# Status_Board_0_4.net
KiCad netlist of a schematic drawn in EAGLE
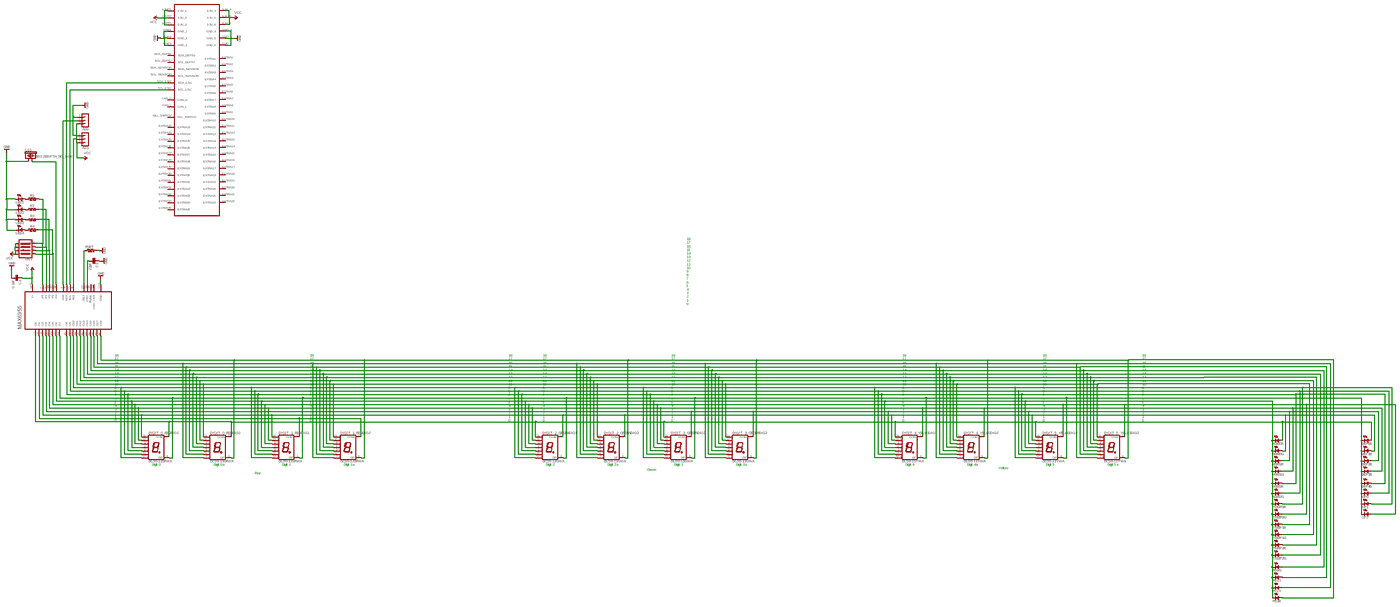
[diagram p0: schematic, sheet 1, overview]
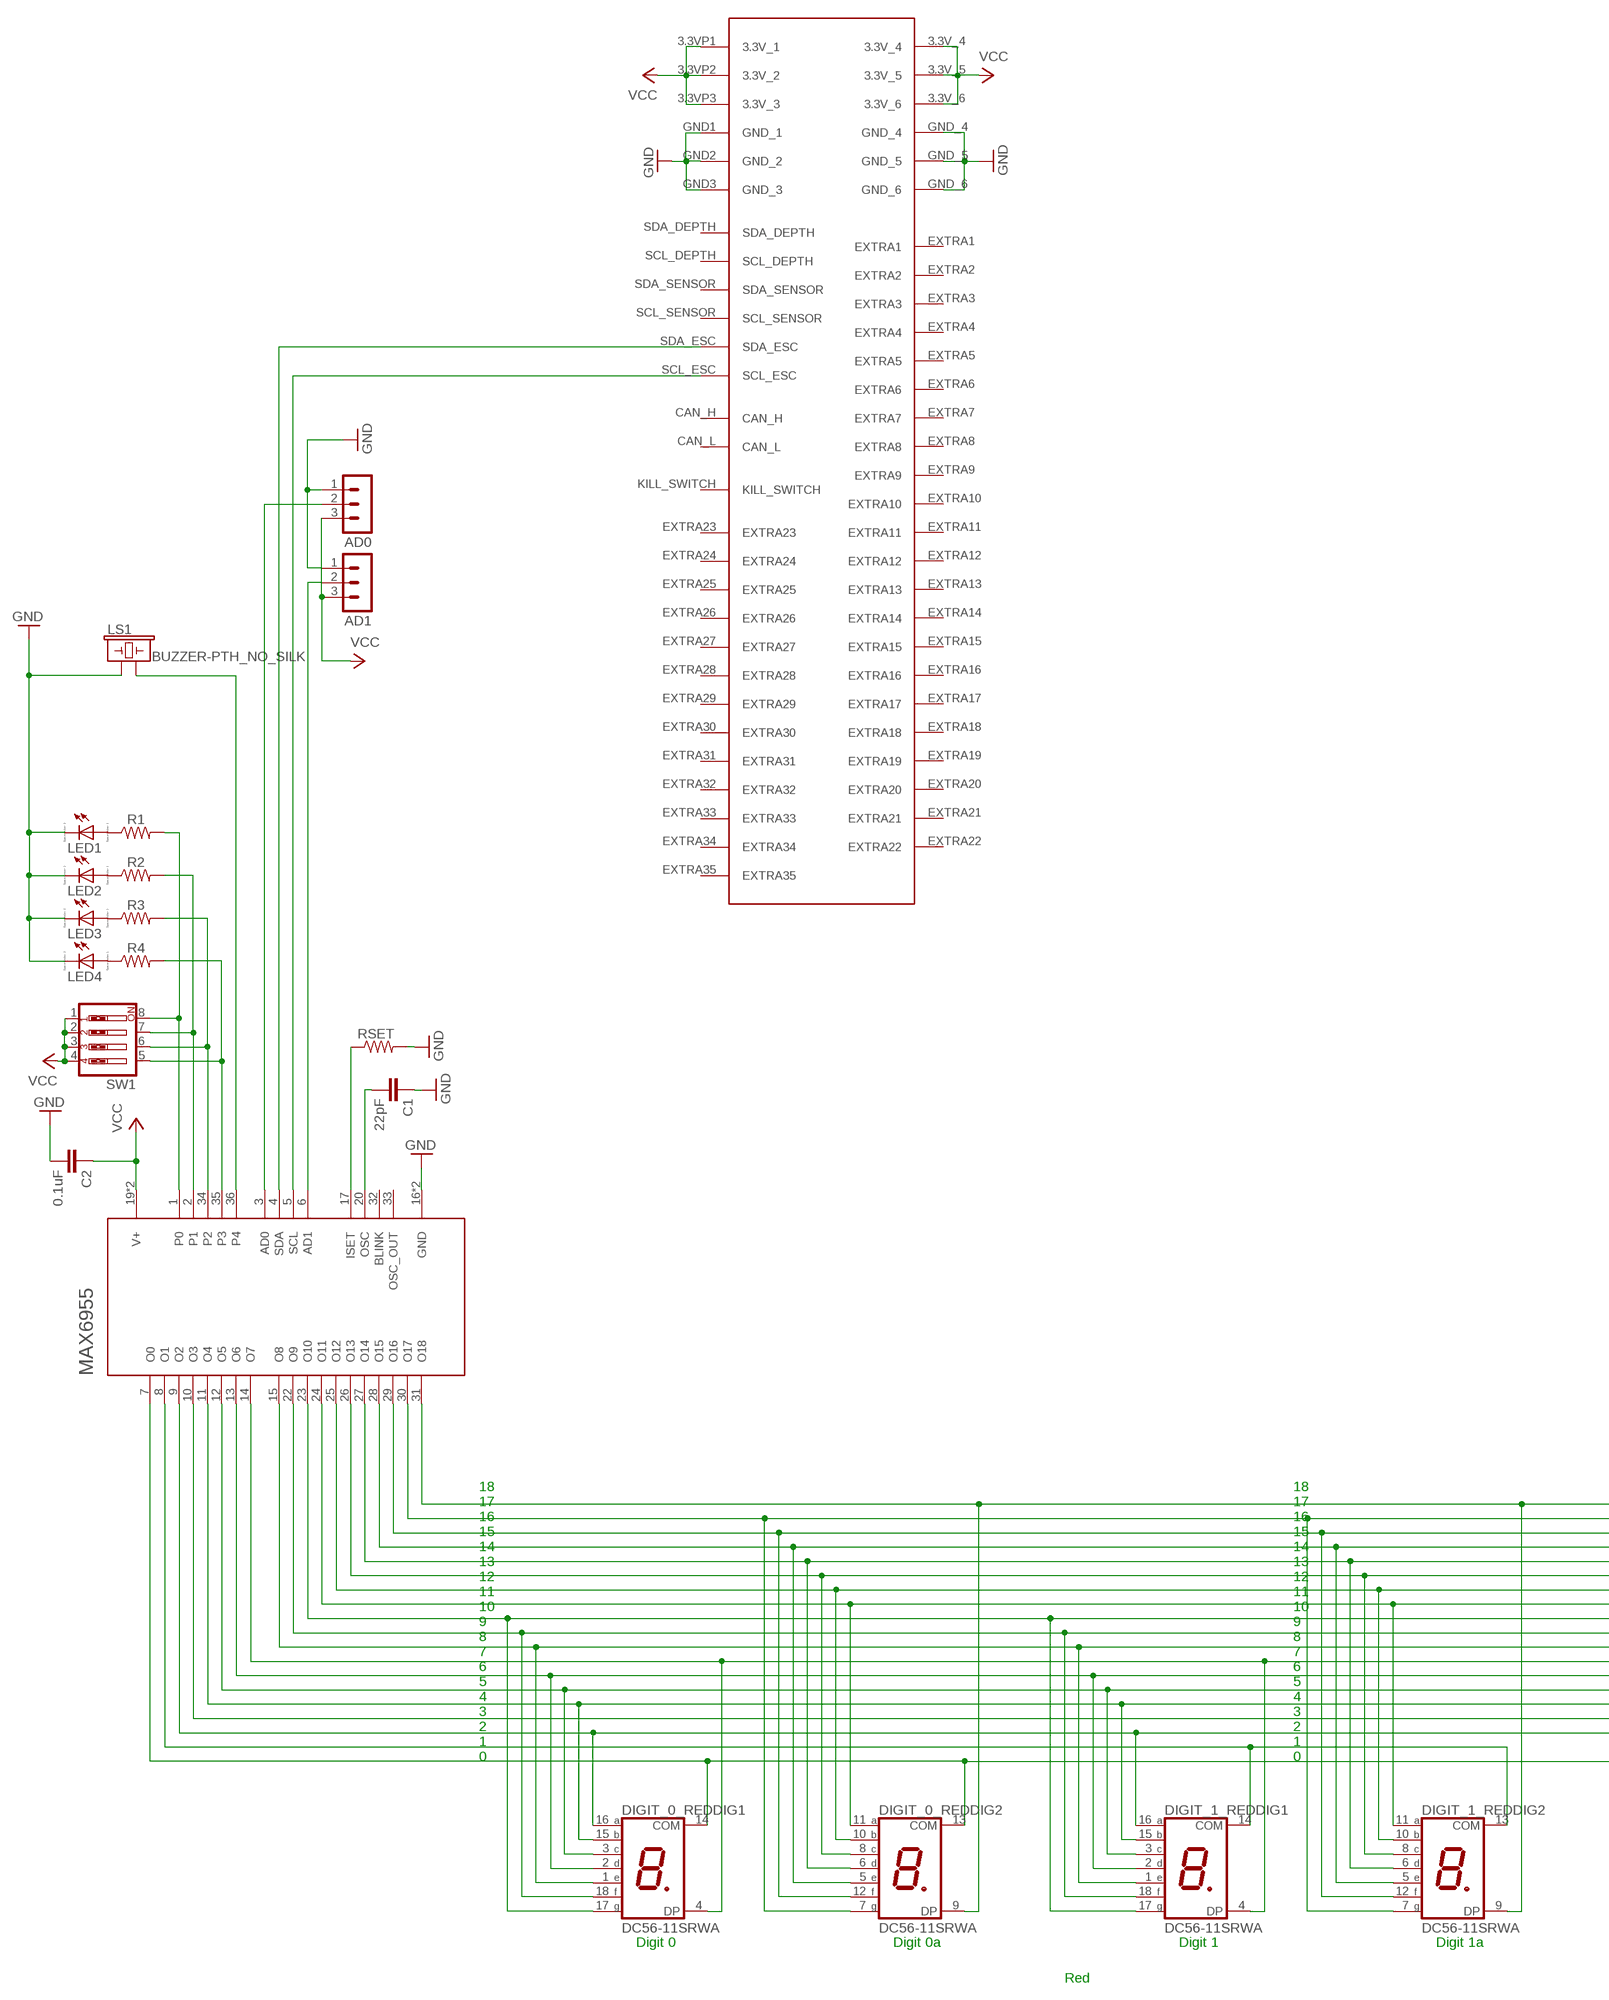
[diagram p1: schematic, sheet 1, part 1 of 4]
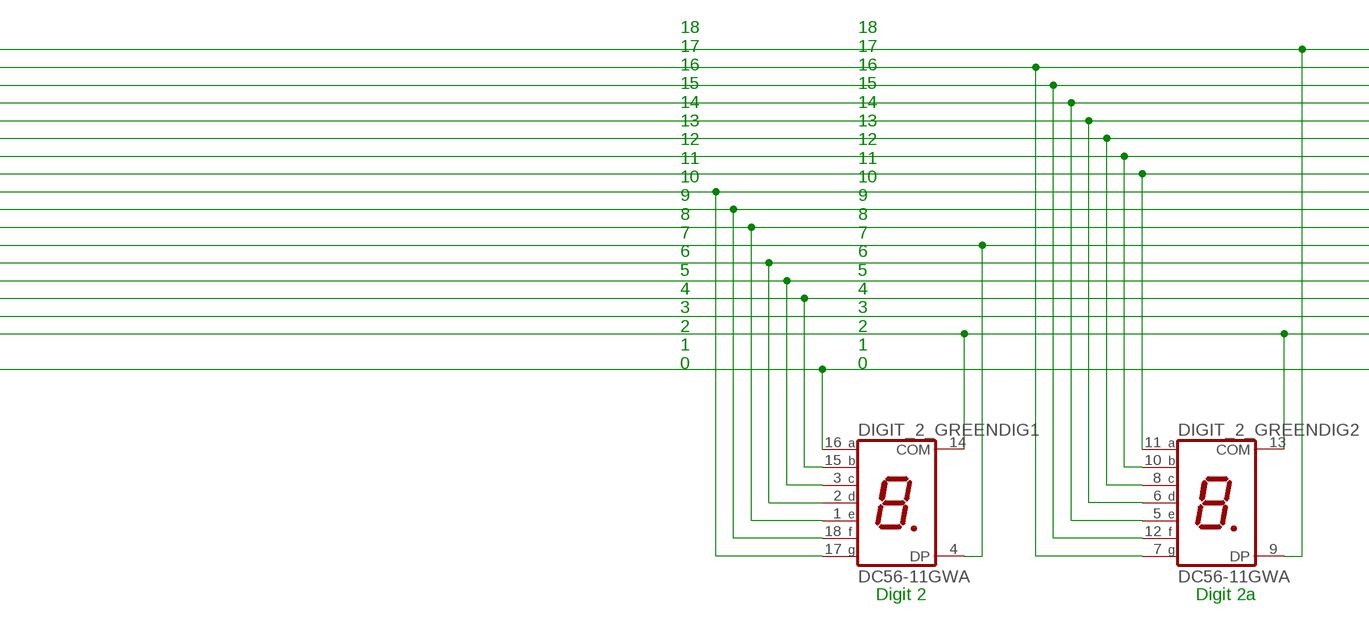
[diagram p2: schematic, sheet 1, part 2 of 4]
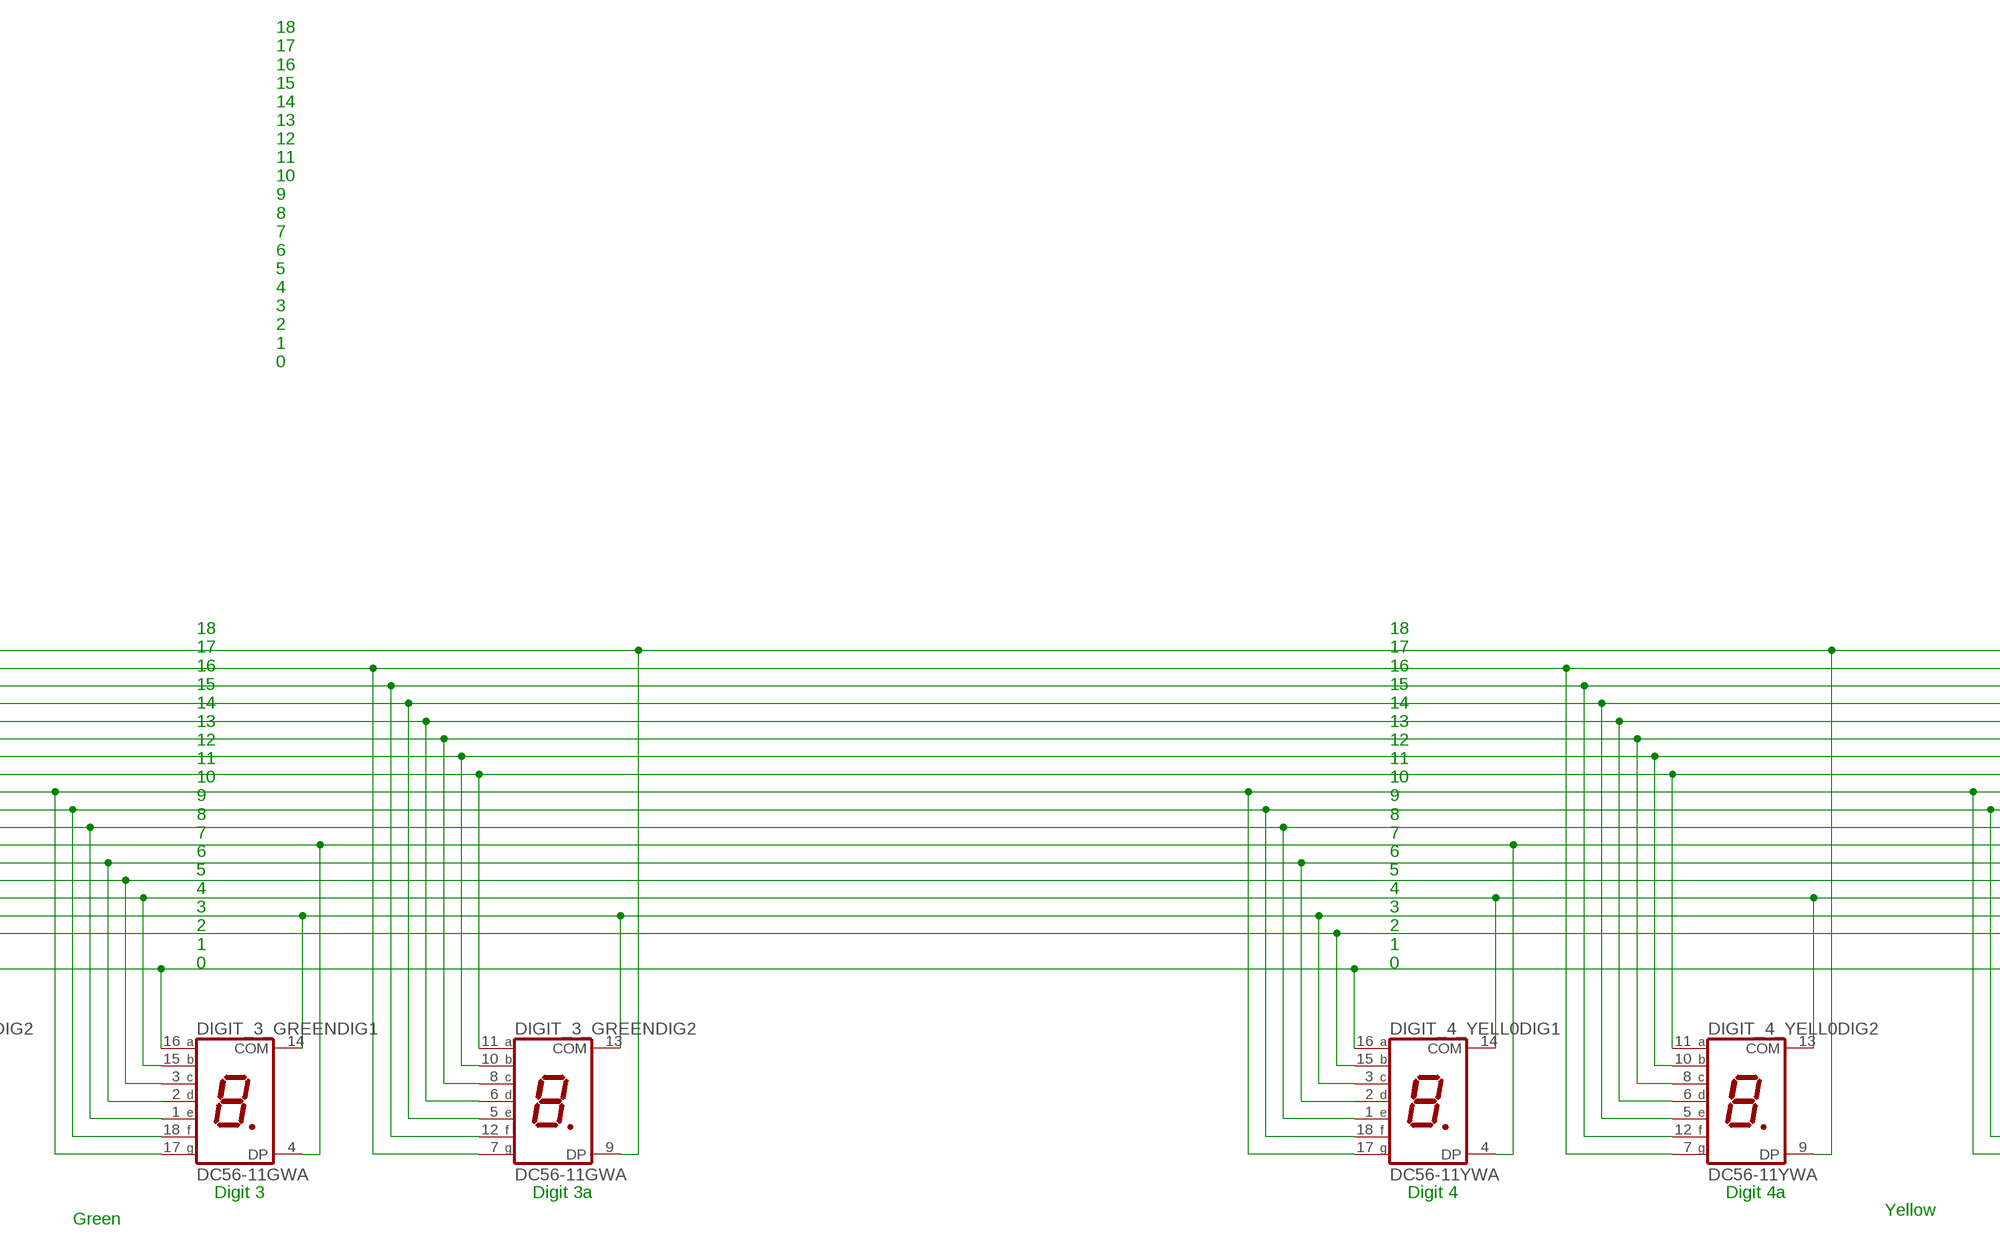
[diagram p3: schematic, sheet 1, part 3 of 4]
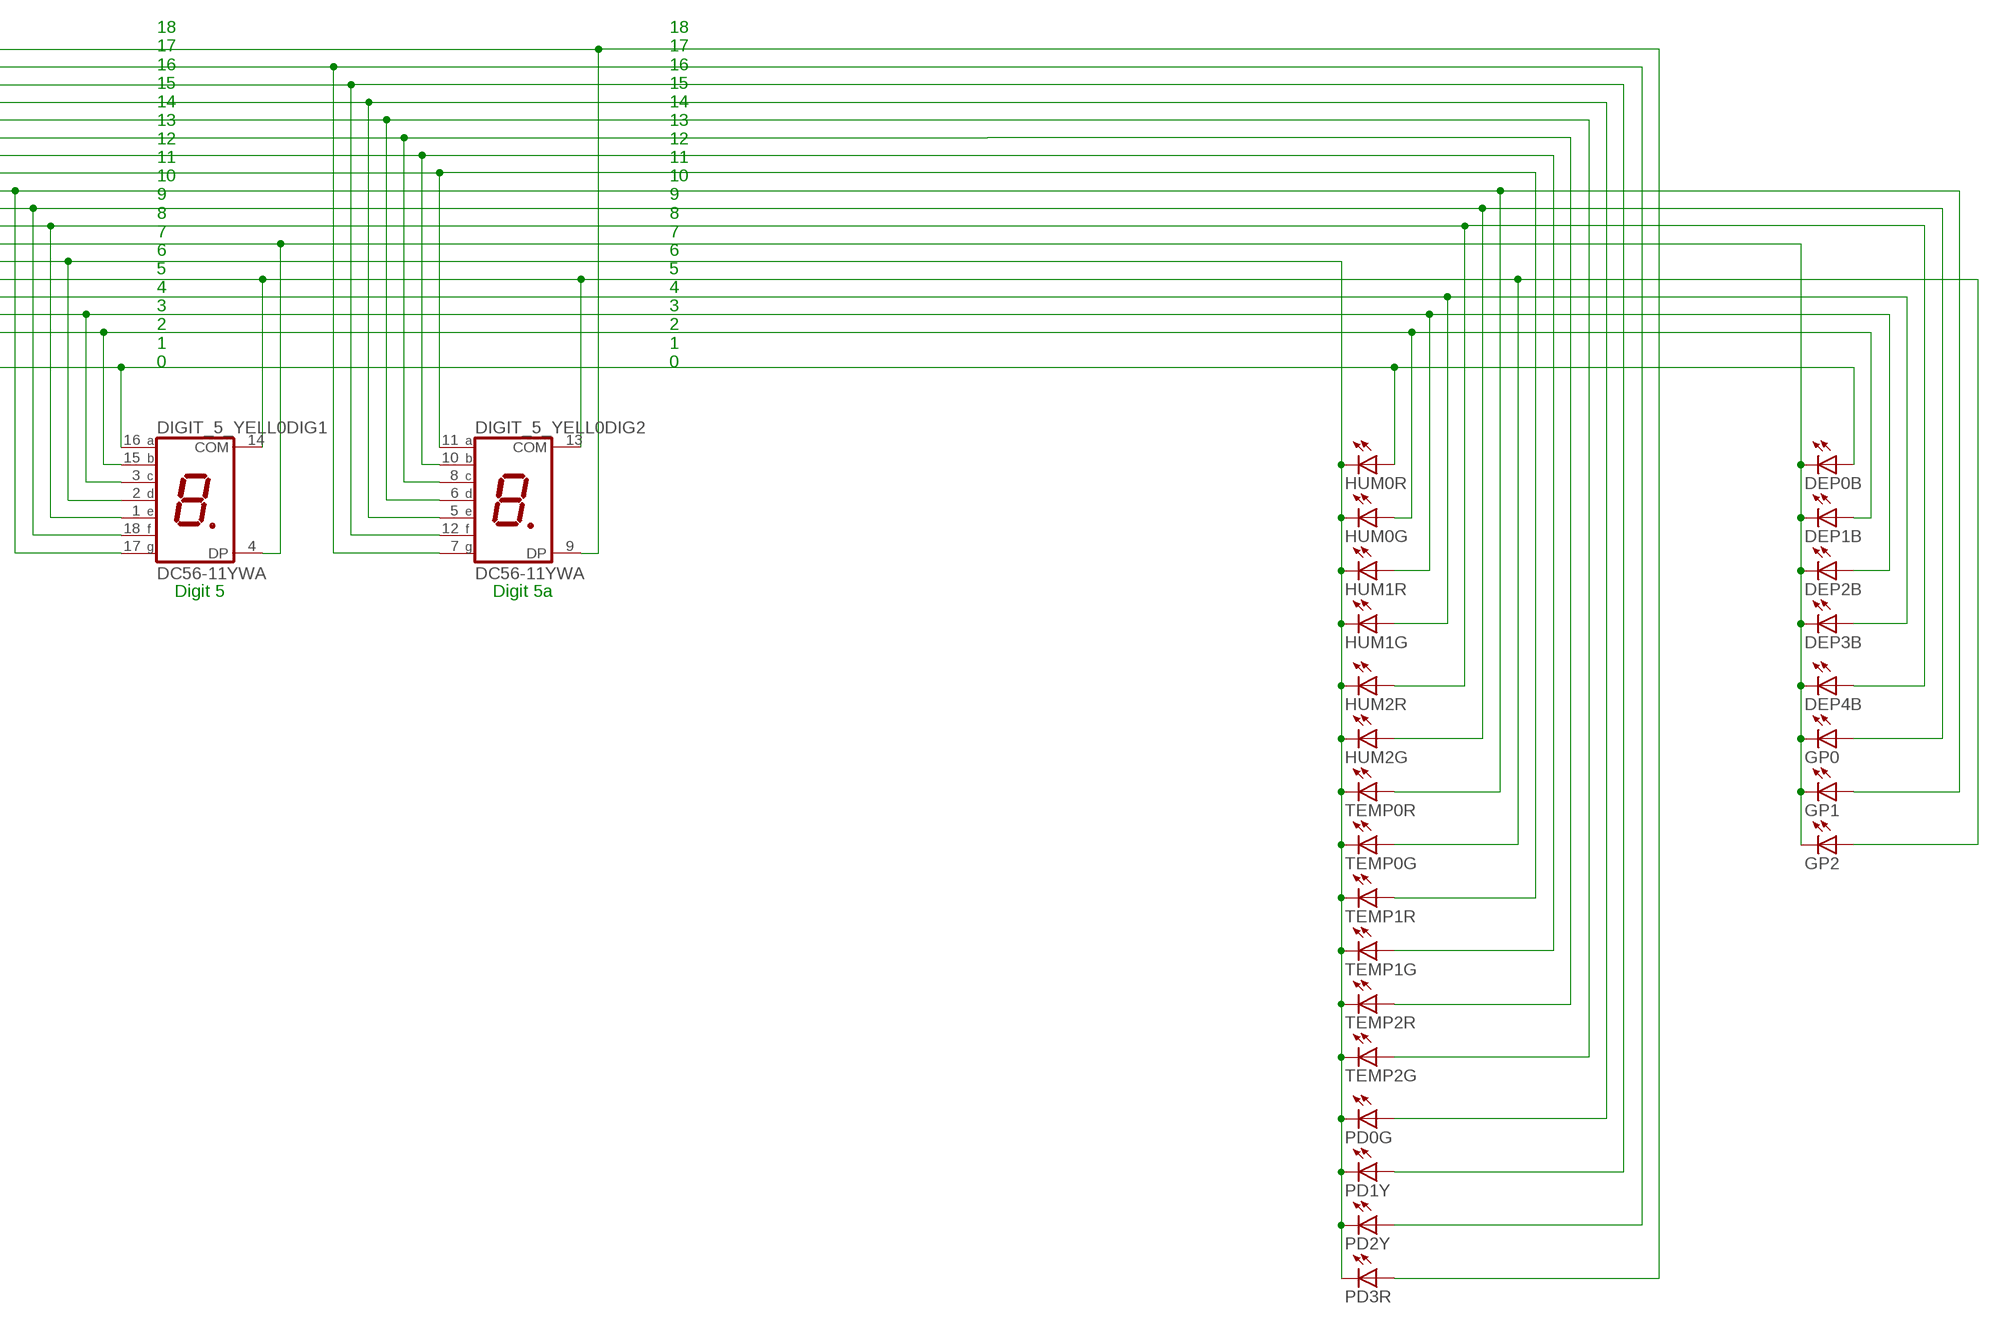
[diagram p4: schematic, sheet 1, part 4 of 4]

(export (version "E")
  (design (tool "Eeschema 10.0.6"))
  (components
    (comp (ref "AD0")
      (value "MA03-1")
      (footprint "eagle-import:MA03-1")
      (libsource (lib "eagle-import") (part "MA03-1"))
    )
    (comp (ref "AD1")
      (value "MA03-1")
      (footprint "eagle-import:MA03-1")
      (libsource (lib "eagle-import") (part "MA03-1"))
    )
    (comp (ref "C1")
      (value "22pF")
      (footprint "eagle-import:CAP-PTH-2.54")
      (libsource (lib "eagle-import") (part "22PF-PTH-2.54MM-200V-5%"))
    )
    (comp (ref "C2")
      (value "0.1uF")
      (footprint "eagle-import:CAP-PTH-SMALL-KIT")
      (libsource (lib "eagle-import") (part "0.1UF-KIT-EZ-50V-20%"))
    )
    (comp (ref "DEP0B")
      (value "LED3MM")
      (footprint "eagle-import:LED3MM")
      (libsource (lib "eagle-import") (part "LED3MM"))
    )
    (comp (ref "DEP1B")
      (value "LED3MM")
      (footprint "eagle-import:LED3MM")
      (libsource (lib "eagle-import") (part "LED3MM"))
    )
    (comp (ref "DEP2B")
      (value "LED3MM")
      (footprint "eagle-import:LED3MM")
      (libsource (lib "eagle-import") (part "LED3MM"))
    )
    (comp (ref "DEP3B")
      (value "LED3MM")
      (footprint "eagle-import:LED3MM")
      (libsource (lib "eagle-import") (part "LED3MM"))
    )
    (comp (ref "DEP4B")
      (value "LED3MM")
      (footprint "eagle-import:LED3MM")
      (libsource (lib "eagle-import") (part "LED3MM"))
    )
    (comp (ref "DIGIT_0_RED")
      (value "DC56-11SRWA")
      (footprint "eagle-import:DA56")
      (libsource (lib "eagle-import") (part "DC56-11SRWA"))
    )
    (comp (ref "DIGIT_1_RED")
      (value "DC56-11SRWA")
      (footprint "eagle-import:DA56")
      (libsource (lib "eagle-import") (part "DC56-11SRWA"))
    )
    (comp (ref "DIGIT_2_GREEN")
      (value "DC56-11GWA")
      (footprint "eagle-import:DA56")
      (libsource (lib "eagle-import") (part "DC56-11GWA"))
    )
    (comp (ref "DIGIT_3_GREEN")
      (value "DC56-11GWA")
      (footprint "eagle-import:DA56")
      (libsource (lib "eagle-import") (part "DC56-11GWA"))
    )
    (comp (ref "DIGIT_4_YELL0")
      (value "DC56-11YWA")
      (footprint "eagle-import:DA56")
      (libsource (lib "eagle-import") (part "DC56-11YWA"))
    )
    (comp (ref "DIGIT_5_YELL0")
      (value "DC56-11YWA")
      (footprint "eagle-import:DA56")
      (libsource (lib "eagle-import") (part "DC56-11YWA"))
    )
    (comp (ref "GP0")
      (value "LED3MM")
      (footprint "eagle-import:LED3MM")
      (libsource (lib "eagle-import") (part "LED3MM"))
    )
    (comp (ref "GP1")
      (value "LED3MM")
      (footprint "eagle-import:LED3MM")
      (libsource (lib "eagle-import") (part "LED3MM"))
    )
    (comp (ref "GP2")
      (value "LED3MM")
      (footprint "eagle-import:LED3MM")
      (libsource (lib "eagle-import") (part "LED3MM"))
    )
    (comp (ref "HUM0G")
      (value "LED3MM")
      (footprint "eagle-import:LED3MM")
      (libsource (lib "eagle-import") (part "LED3MM"))
    )
    (comp (ref "HUM0R")
      (value "LED3MM")
      (footprint "eagle-import:LED3MM")
      (libsource (lib "eagle-import") (part "LED3MM"))
    )
    (comp (ref "HUM1G")
      (value "LED3MM")
      (footprint "eagle-import:LED3MM")
      (libsource (lib "eagle-import") (part "LED3MM"))
    )
    (comp (ref "HUM1R")
      (value "LED3MM")
      (footprint "eagle-import:LED3MM")
      (libsource (lib "eagle-import") (part "LED3MM"))
    )
    (comp (ref "HUM2G")
      (value "LED3MM")
      (footprint "eagle-import:LED3MM")
      (libsource (lib "eagle-import") (part "LED3MM"))
    )
    (comp (ref "HUM2R")
      (value "LED3MM")
      (footprint "eagle-import:LED3MM")
      (libsource (lib "eagle-import") (part "LED3MM"))
    )
    (comp (ref "LED1")
      (value "LED_ESML0603")
      (footprint "eagle-import:LED_SML0603")
      (libsource (lib "eagle-import") (part "LED_ESML0603"))
    )
    (comp (ref "LED2")
      (value "LED_ESML0603")
      (footprint "eagle-import:LED_SML0603")
      (libsource (lib "eagle-import") (part "LED_ESML0603"))
    )
    (comp (ref "LED3")
      (value "LED_ESML0603")
      (footprint "eagle-import:LED_SML0603")
      (libsource (lib "eagle-import") (part "LED_ESML0603"))
    )
    (comp (ref "LED4")
      (value "LED_ESML0603")
      (footprint "eagle-import:LED_SML0603")
      (libsource (lib "eagle-import") (part "LED_ESML0603"))
    )
    (comp (ref "LS1")
      (value "BUZZER-PTH_NO_SILK")
      (footprint "eagle-import:BUZZER-12MM-NS")
      (libsource (lib "eagle-import") (part "BUZZER-PTH_NO_SILK"))
    )
    (comp (ref "MAX6955")
      (value "MAX6955")
      (footprint "eagle-import:SSOP36")
      (libsource (lib "eagle-import") (part "MAX6955"))
    )
    (comp (ref "PD0G")
      (value "LED3MM")
      (footprint "eagle-import:LED3MM")
      (libsource (lib "eagle-import") (part "LED3MM"))
    )
    (comp (ref "PD1Y")
      (value "LED3MM")
      (footprint "eagle-import:LED3MM")
      (libsource (lib "eagle-import") (part "LED3MM"))
    )
    (comp (ref "PD2Y")
      (value "LED3MM")
      (footprint "eagle-import:LED3MM")
      (libsource (lib "eagle-import") (part "LED3MM"))
    )
    (comp (ref "PD3R")
      (value "LED3MM")
      (footprint "eagle-import:LED3MM")
      (libsource (lib "eagle-import") (part "LED3MM"))
    )
    (comp (ref "R1")
      (value "68OHM-0603-1/10W-1%")
      (footprint "eagle-import:0603")
      (libsource (lib "eagle-import") (part "68OHM-0603-1/10W-1%"))
    )
    (comp (ref "R2")
      (value "68OHM-0603-1/10W-1%")
      (footprint "eagle-import:0603")
      (libsource (lib "eagle-import") (part "68OHM-0603-1/10W-1%"))
    )
    (comp (ref "R3")
      (value "68OHM-0603-1/10W-1%")
      (footprint "eagle-import:0603")
      (libsource (lib "eagle-import") (part "68OHM-0603-1/10W-1%"))
    )
    (comp (ref "R4")
      (value "68OHM-0603-1/10W-1%")
      (footprint "eagle-import:0603")
      (libsource (lib "eagle-import") (part "68OHM-0603-1/10W-1%"))
    )
    (comp (ref "RSET")
      (value "R-US_0207/12")
      (footprint "eagle-import:0207_12")
      (libsource (lib "eagle-import") (part "R-US_0207/12"))
    )
    (comp (ref "SW1")
      (value "SW_DIP-4")
      (footprint "eagle-import:EDG-04")
      (libsource (lib "eagle-import") (part "SW_DIP-4"))
    )
    (comp (ref "TEMP0G")
      (value "LED3MM")
      (footprint "eagle-import:LED3MM")
      (libsource (lib "eagle-import") (part "LED3MM"))
    )
    (comp (ref "TEMP0R")
      (value "LED3MM")
      (footprint "eagle-import:LED3MM")
      (libsource (lib "eagle-import") (part "LED3MM"))
    )
    (comp (ref "TEMP1G")
      (value "LED3MM")
      (footprint "eagle-import:LED3MM")
      (libsource (lib "eagle-import") (part "LED3MM"))
    )
    (comp (ref "TEMP1R")
      (value "LED3MM")
      (footprint "eagle-import:LED3MM")
      (libsource (lib "eagle-import") (part "LED3MM"))
    )
    (comp (ref "TEMP2G")
      (value "LED3MM")
      (footprint "eagle-import:LED3MM")
      (libsource (lib "eagle-import") (part "LED3MM"))
    )
    (comp (ref "TEMP2R")
      (value "LED3MM")
      (footprint "eagle-import:LED3MM")
      (libsource (lib "eagle-import") (part "LED3MM"))
    )
    (comp (ref "U$2")
      (value "5530843")
      (footprint "eagle-import:5530843-6-BOARDFINGERS")
      (libsource (lib "eagle-import") (part "5530843"))
    )
  )
  (nets
    (net (code "1") (name "GND") (class "Default")
      (node (ref "AD0") (pin "1") (pinfunction "1_1") (pintype "passive"))
      (node (ref "AD1") (pin "1") (pinfunction "1_1") (pintype "passive"))
      (node (ref "C1") (pin "1") (pinfunction "1_1") (pintype "passive"))
      (node (ref "C2") (pin "2") (pinfunction "2_2") (pintype "passive"))
      (node (ref "LED1") (pin "C") (pinfunction "C_C") (pintype "passive"))
      (node (ref "LED2") (pin "C") (pinfunction "C_C") (pintype "passive"))
      (node (ref "LED3") (pin "C") (pinfunction "C_C") (pintype "passive"))
      (node (ref "LED4") (pin "C") (pinfunction "C_C") (pintype "passive"))
      (node (ref "LS1") (pin "+") (pinfunction "1_+") (pintype "passive"))
      (node (ref "MAX6955") (pin "16") (pinfunction "GND_16") (pintype "bidirectional"))
      (node (ref "MAX6955") (pin "18") (pinfunction "GND_18") (pintype "bidirectional"))
      (node (ref "RSET") (pin "2") (pinfunction "2_2") (pintype "passive"))
      (node (ref "U$2") (pin "GND1") (pinfunction "GND_1_GND1") (pintype "bidirectional"))
      (node (ref "U$2") (pin "GND2") (pinfunction "GND_2_GND2") (pintype "bidirectional"))
      (node (ref "U$2") (pin "GND3") (pinfunction "GND_3_GND3") (pintype "bidirectional"))
      (node (ref "U$2") (pin "GND_4") (pinfunction "GND_4_GND_4") (pintype "bidirectional"))
      (node (ref "U$2") (pin "GND_5") (pinfunction "GND_5_GND_5") (pintype "bidirectional"))
      (node (ref "U$2") (pin "GND_6") (pinfunction "GND_6_GND_6") (pintype "bidirectional"))
    )
    (net (code "2") (name "Net-(DEP0B-C)") (class "Default")
      (node (ref "DEP0B") (pin "K") (pinfunction "C_K") (pintype "passive"))
      (node (ref "DEP1B") (pin "K") (pinfunction "C_K") (pintype "passive"))
      (node (ref "DEP2B") (pin "K") (pinfunction "C_K") (pintype "passive"))
      (node (ref "DEP3B") (pin "K") (pinfunction "C_K") (pintype "passive"))
      (node (ref "DEP4B") (pin "K") (pinfunction "C_K") (pintype "passive"))
      (node (ref "DIGIT_0_RED") (pin "4") (pinfunction "DP_4") (pintype "passive"))
      (node (ref "DIGIT_1_RED") (pin "4") (pinfunction "DP_4") (pintype "passive"))
      (node (ref "DIGIT_2_GREEN") (pin "4") (pinfunction "DP_4") (pintype "passive"))
      (node (ref "DIGIT_3_GREEN") (pin "4") (pinfunction "DP_4") (pintype "passive"))
      (node (ref "DIGIT_4_YELL0") (pin "4") (pinfunction "DP_4") (pintype "passive"))
      (node (ref "DIGIT_5_YELL0") (pin "4") (pinfunction "DP_4") (pintype "passive"))
      (node (ref "GP0") (pin "K") (pinfunction "C_K") (pintype "passive"))
      (node (ref "GP1") (pin "K") (pinfunction "C_K") (pintype "passive"))
      (node (ref "GP2") (pin "K") (pinfunction "C_K") (pintype "passive"))
      (node (ref "MAX6955") (pin "14") (pinfunction "O7_14") (pintype "bidirectional"))
    )
    (net (code "3") (name "Net-(DIGIT_0_REDA-A)") (class "Default")
      (node (ref "DEP1B") (pin "A") (pinfunction "A_A") (pintype "passive"))
      (node (ref "DIGIT_0_RED") (pin "16") (pinfunction "A_16") (pintype "passive"))
      (node (ref "DIGIT_1_RED") (pin "16") (pinfunction "A_16") (pintype "passive"))
      (node (ref "DIGIT_2_GREEN") (pin "13") (pinfunction "COM_13") (pintype "passive"))
      (node (ref "DIGIT_2_GREEN") (pin "14") (pinfunction "COM_14") (pintype "passive"))
      (node (ref "DIGIT_4_YELL0") (pin "15") (pinfunction "B_15") (pintype "passive"))
      (node (ref "DIGIT_5_YELL0") (pin "15") (pinfunction "B_15") (pintype "passive"))
      (node (ref "HUM0G") (pin "A") (pinfunction "A_A") (pintype "passive"))
      (node (ref "MAX6955") (pin "9") (pinfunction "O2_9") (pintype "bidirectional"))
    )
    (net (code "4") (name "Net-(DIGIT_0_REDA-B)") (class "Default")
      (node (ref "DEP3B") (pin "A") (pinfunction "A_A") (pintype "passive"))
      (node (ref "DIGIT_0_RED") (pin "15") (pinfunction "B_15") (pintype "passive"))
      (node (ref "DIGIT_1_RED") (pin "15") (pinfunction "B_15") (pintype "passive"))
      (node (ref "DIGIT_2_GREEN") (pin "15") (pinfunction "B_15") (pintype "passive"))
      (node (ref "DIGIT_3_GREEN") (pin "15") (pinfunction "B_15") (pintype "passive"))
      (node (ref "DIGIT_4_YELL0") (pin "13") (pinfunction "COM_13") (pintype "passive"))
      (node (ref "DIGIT_4_YELL0") (pin "14") (pinfunction "COM_14") (pintype "passive"))
      (node (ref "HUM1G") (pin "A") (pinfunction "A_A") (pintype "passive"))
      (node (ref "MAX6955") (pin "11") (pinfunction "O4_11") (pintype "bidirectional"))
    )
    (net (code "5") (name "Net-(DIGIT_0_REDA-C)") (class "Default")
      (node (ref "DIGIT_0_RED") (pin "3") (pinfunction "C_3") (pintype "passive"))
      (node (ref "DIGIT_1_RED") (pin "3") (pinfunction "C_3") (pintype "passive"))
      (node (ref "DIGIT_2_GREEN") (pin "3") (pinfunction "C_3") (pintype "passive"))
      (node (ref "DIGIT_3_GREEN") (pin "3") (pinfunction "C_3") (pintype "passive"))
      (node (ref "DIGIT_5_YELL0") (pin "13") (pinfunction "COM_13") (pintype "passive"))
      (node (ref "DIGIT_5_YELL0") (pin "14") (pinfunction "COM_14") (pintype "passive"))
      (node (ref "GP2") (pin "A") (pinfunction "A_A") (pintype "passive"))
      (node (ref "MAX6955") (pin "12") (pinfunction "O5_12") (pintype "bidirectional"))
      (node (ref "TEMP0G") (pin "A") (pinfunction "A_A") (pintype "passive"))
    )
    (net (code "6") (name "Net-(DIGIT_0_REDA-COM)") (class "Default")
      (node (ref "DEP0B") (pin "A") (pinfunction "A_A") (pintype "passive"))
      (node (ref "DIGIT_0_RED") (pin "13") (pinfunction "COM_13") (pintype "passive"))
      (node (ref "DIGIT_0_RED") (pin "14") (pinfunction "COM_14") (pintype "passive"))
      (node (ref "DIGIT_2_GREEN") (pin "16") (pinfunction "A_16") (pintype "passive"))
      (node (ref "DIGIT_3_GREEN") (pin "16") (pinfunction "A_16") (pintype "passive"))
      (node (ref "DIGIT_4_YELL0") (pin "16") (pinfunction "A_16") (pintype "passive"))
      (node (ref "DIGIT_5_YELL0") (pin "16") (pinfunction "A_16") (pintype "passive"))
      (node (ref "HUM0R") (pin "A") (pinfunction "A_A") (pintype "passive"))
      (node (ref "MAX6955") (pin "7") (pinfunction "O0_7") (pintype "bidirectional"))
    )
    (net (code "7") (name "Net-(DIGIT_0_REDA-D)") (class "Default")
      (node (ref "DIGIT_0_RED") (pin "2") (pinfunction "D_2") (pintype "passive"))
      (node (ref "DIGIT_1_RED") (pin "2") (pinfunction "D_2") (pintype "passive"))
      (node (ref "DIGIT_2_GREEN") (pin "2") (pinfunction "D_2") (pintype "passive"))
      (node (ref "DIGIT_3_GREEN") (pin "2") (pinfunction "D_2") (pintype "passive"))
      (node (ref "DIGIT_4_YELL0") (pin "2") (pinfunction "D_2") (pintype "passive"))
      (node (ref "DIGIT_5_YELL0") (pin "2") (pinfunction "D_2") (pintype "passive"))
      (node (ref "HUM0G") (pin "K") (pinfunction "C_K") (pintype "passive"))
      (node (ref "HUM0R") (pin "K") (pinfunction "C_K") (pintype "passive"))
      (node (ref "HUM1G") (pin "K") (pinfunction "C_K") (pintype "passive"))
      (node (ref "HUM1R") (pin "K") (pinfunction "C_K") (pintype "passive"))
      (node (ref "HUM2G") (pin "K") (pinfunction "C_K") (pintype "passive"))
      (node (ref "HUM2R") (pin "K") (pinfunction "C_K") (pintype "passive"))
      (node (ref "MAX6955") (pin "13") (pinfunction "O6_13") (pintype "bidirectional"))
      (node (ref "PD0G") (pin "K") (pinfunction "C_K") (pintype "passive"))
      (node (ref "PD1Y") (pin "K") (pinfunction "C_K") (pintype "passive"))
      (node (ref "PD2Y") (pin "K") (pinfunction "C_K") (pintype "passive"))
      (node (ref "PD3R") (pin "K") (pinfunction "C_K") (pintype "passive"))
      (node (ref "TEMP0G") (pin "K") (pinfunction "C_K") (pintype "passive"))
      (node (ref "TEMP0R") (pin "K") (pinfunction "C_K") (pintype "passive"))
      (node (ref "TEMP1G") (pin "K") (pinfunction "C_K") (pintype "passive"))
      (node (ref "TEMP1R") (pin "K") (pinfunction "C_K") (pintype "passive"))
      (node (ref "TEMP2G") (pin "K") (pinfunction "C_K") (pintype "passive"))
      (node (ref "TEMP2R") (pin "K") (pinfunction "C_K") (pintype "passive"))
    )
    (net (code "8") (name "Net-(DIGIT_0_REDA-E)") (class "Default")
      (node (ref "DEP4B") (pin "A") (pinfunction "A_A") (pintype "passive"))
      (node (ref "DIGIT_0_RED") (pin "1") (pinfunction "E_1") (pintype "passive"))
      (node (ref "DIGIT_1_RED") (pin "1") (pinfunction "E_1") (pintype "passive"))
      (node (ref "DIGIT_2_GREEN") (pin "1") (pinfunction "E_1") (pintype "passive"))
      (node (ref "DIGIT_3_GREEN") (pin "1") (pinfunction "E_1") (pintype "passive"))
      (node (ref "DIGIT_4_YELL0") (pin "1") (pinfunction "E_1") (pintype "passive"))
      (node (ref "DIGIT_5_YELL0") (pin "1") (pinfunction "E_1") (pintype "passive"))
      (node (ref "HUM2R") (pin "A") (pinfunction "A_A") (pintype "passive"))
      (node (ref "MAX6955") (pin "15") (pinfunction "O8_15") (pintype "bidirectional"))
    )
    (net (code "9") (name "Net-(DIGIT_0_REDA-F)") (class "Default")
      (node (ref "DIGIT_0_RED") (pin "18") (pinfunction "F_18") (pintype "passive"))
      (node (ref "DIGIT_1_RED") (pin "18") (pinfunction "F_18") (pintype "passive"))
      (node (ref "DIGIT_2_GREEN") (pin "18") (pinfunction "F_18") (pintype "passive"))
      (node (ref "DIGIT_3_GREEN") (pin "18") (pinfunction "F_18") (pintype "passive"))
      (node (ref "DIGIT_4_YELL0") (pin "18") (pinfunction "F_18") (pintype "passive"))
      (node (ref "DIGIT_5_YELL0") (pin "18") (pinfunction "F_18") (pintype "passive"))
      (node (ref "GP0") (pin "A") (pinfunction "A_A") (pintype "passive"))
      (node (ref "HUM2G") (pin "A") (pinfunction "A_A") (pintype "passive"))
      (node (ref "MAX6955") (pin "22") (pinfunction "O9_22") (pintype "bidirectional"))
    )
    (net (code "10") (name "Net-(DIGIT_0_REDA-G)") (class "Default")
      (node (ref "DIGIT_0_RED") (pin "17") (pinfunction "G_17") (pintype "passive"))
      (node (ref "DIGIT_1_RED") (pin "17") (pinfunction "G_17") (pintype "passive"))
      (node (ref "DIGIT_2_GREEN") (pin "17") (pinfunction "G_17") (pintype "passive"))
      (node (ref "DIGIT_3_GREEN") (pin "17") (pinfunction "G_17") (pintype "passive"))
      (node (ref "DIGIT_4_YELL0") (pin "17") (pinfunction "G_17") (pintype "passive"))
      (node (ref "DIGIT_5_YELL0") (pin "17") (pinfunction "G_17") (pintype "passive"))
      (node (ref "GP1") (pin "A") (pinfunction "A_A") (pintype "passive"))
      (node (ref "MAX6955") (pin "23") (pinfunction "O10_23") (pintype "bidirectional"))
      (node (ref "TEMP0R") (pin "A") (pinfunction "A_A") (pintype "passive"))
    )
    (net (code "11") (name "Net-(DIGIT_0_REDB-A)") (class "Default")
      (node (ref "DIGIT_0_RED") (pin "11") (pinfunction "A_11") (pintype "passive"))
      (node (ref "DIGIT_1_RED") (pin "11") (pinfunction "A_11") (pintype "passive"))
      (node (ref "DIGIT_2_GREEN") (pin "11") (pinfunction "A_11") (pintype "passive"))
      (node (ref "DIGIT_3_GREEN") (pin "11") (pinfunction "A_11") (pintype "passive"))
      (node (ref "DIGIT_4_YELL0") (pin "11") (pinfunction "A_11") (pintype "passive"))
      (node (ref "DIGIT_5_YELL0") (pin "11") (pinfunction "A_11") (pintype "passive"))
      (node (ref "MAX6955") (pin "24") (pinfunction "O11_24") (pintype "bidirectional"))
      (node (ref "TEMP1R") (pin "A") (pinfunction "A_A") (pintype "passive"))
    )
    (net (code "12") (name "Net-(DIGIT_0_REDB-B)") (class "Default")
      (node (ref "DIGIT_0_RED") (pin "10") (pinfunction "B_10") (pintype "passive"))
      (node (ref "DIGIT_1_RED") (pin "10") (pinfunction "B_10") (pintype "passive"))
      (node (ref "DIGIT_2_GREEN") (pin "10") (pinfunction "B_10") (pintype "passive"))
      (node (ref "DIGIT_3_GREEN") (pin "10") (pinfunction "B_10") (pintype "passive"))
      (node (ref "DIGIT_4_YELL0") (pin "10") (pinfunction "B_10") (pintype "passive"))
      (node (ref "DIGIT_5_YELL0") (pin "10") (pinfunction "B_10") (pintype "passive"))
      (node (ref "MAX6955") (pin "25") (pinfunction "O12_25") (pintype "bidirectional"))
      (node (ref "TEMP1G") (pin "A") (pinfunction "A_A") (pintype "passive"))
    )
    (net (code "13") (name "Net-(DIGIT_0_REDB-C)") (class "Default")
      (node (ref "DIGIT_0_RED") (pin "8") (pinfunction "C_8") (pintype "passive"))
      (node (ref "DIGIT_1_RED") (pin "8") (pinfunction "C_8") (pintype "passive"))
      (node (ref "DIGIT_2_GREEN") (pin "8") (pinfunction "C_8") (pintype "passive"))
      (node (ref "DIGIT_3_GREEN") (pin "8") (pinfunction "C_8") (pintype "passive"))
      (node (ref "DIGIT_4_YELL0") (pin "8") (pinfunction "C_8") (pintype "passive"))
      (node (ref "DIGIT_5_YELL0") (pin "8") (pinfunction "C_8") (pintype "passive"))
      (node (ref "MAX6955") (pin "26") (pinfunction "O13_26") (pintype "bidirectional"))
      (node (ref "TEMP2R") (pin "A") (pinfunction "A_A") (pintype "passive"))
    )
    (net (code "14") (name "Net-(DIGIT_0_REDB-D)") (class "Default")
      (node (ref "DIGIT_0_RED") (pin "6") (pinfunction "D_6") (pintype "passive"))
      (node (ref "DIGIT_1_RED") (pin "6") (pinfunction "D_6") (pintype "passive"))
      (node (ref "DIGIT_2_GREEN") (pin "6") (pinfunction "D_6") (pintype "passive"))
      (node (ref "DIGIT_3_GREEN") (pin "6") (pinfunction "D_6") (pintype "passive"))
      (node (ref "DIGIT_4_YELL0") (pin "6") (pinfunction "D_6") (pintype "passive"))
      (node (ref "DIGIT_5_YELL0") (pin "6") (pinfunction "D_6") (pintype "passive"))
      (node (ref "MAX6955") (pin "27") (pinfunction "O14_27") (pintype "bidirectional"))
      (node (ref "TEMP2G") (pin "A") (pinfunction "A_A") (pintype "passive"))
    )
    (net (code "15") (name "Net-(DIGIT_0_REDB-DP)") (class "Default")
      (node (ref "DIGIT_0_RED") (pin "9") (pinfunction "DP_9") (pintype "passive"))
      (node (ref "DIGIT_1_RED") (pin "9") (pinfunction "DP_9") (pintype "passive"))
      (node (ref "DIGIT_2_GREEN") (pin "9") (pinfunction "DP_9") (pintype "passive"))
      (node (ref "DIGIT_3_GREEN") (pin "9") (pinfunction "DP_9") (pintype "passive"))
      (node (ref "DIGIT_4_YELL0") (pin "9") (pinfunction "DP_9") (pintype "passive"))
      (node (ref "DIGIT_5_YELL0") (pin "9") (pinfunction "DP_9") (pintype "passive"))
      (node (ref "MAX6955") (pin "31") (pinfunction "O18_31") (pintype "bidirectional"))
      (node (ref "PD3R") (pin "A") (pinfunction "A_A") (pintype "passive"))
    )
    (net (code "16") (name "Net-(DIGIT_0_REDB-E)") (class "Default")
      (node (ref "DIGIT_0_RED") (pin "5") (pinfunction "E_5") (pintype "passive"))
      (node (ref "DIGIT_1_RED") (pin "5") (pinfunction "E_5") (pintype "passive"))
      (node (ref "DIGIT_2_GREEN") (pin "5") (pinfunction "E_5") (pintype "passive"))
      (node (ref "DIGIT_3_GREEN") (pin "5") (pinfunction "E_5") (pintype "passive"))
      (node (ref "DIGIT_4_YELL0") (pin "5") (pinfunction "E_5") (pintype "passive"))
      (node (ref "DIGIT_5_YELL0") (pin "5") (pinfunction "E_5") (pintype "passive"))
      (node (ref "MAX6955") (pin "28") (pinfunction "O15_28") (pintype "bidirectional"))
      (node (ref "PD0G") (pin "A") (pinfunction "A_A") (pintype "passive"))
    )
    (net (code "17") (name "Net-(DIGIT_0_REDB-F)") (class "Default")
      (node (ref "DIGIT_0_RED") (pin "12") (pinfunction "F_12") (pintype "passive"))
      (node (ref "DIGIT_1_RED") (pin "12") (pinfunction "F_12") (pintype "passive"))
      (node (ref "DIGIT_2_GREEN") (pin "12") (pinfunction "F_12") (pintype "passive"))
      (node (ref "DIGIT_3_GREEN") (pin "12") (pinfunction "F_12") (pintype "passive"))
      (node (ref "DIGIT_4_YELL0") (pin "12") (pinfunction "F_12") (pintype "passive"))
      (node (ref "DIGIT_5_YELL0") (pin "12") (pinfunction "F_12") (pintype "passive"))
      (node (ref "MAX6955") (pin "29") (pinfunction "O16_29") (pintype "bidirectional"))
      (node (ref "PD1Y") (pin "A") (pinfunction "A_A") (pintype "passive"))
    )
    (net (code "18") (name "Net-(DIGIT_0_REDB-G)") (class "Default")
      (node (ref "DIGIT_0_RED") (pin "7") (pinfunction "G_7") (pintype "passive"))
      (node (ref "DIGIT_1_RED") (pin "7") (pinfunction "G_7") (pintype "passive"))
      (node (ref "DIGIT_2_GREEN") (pin "7") (pinfunction "G_7") (pintype "passive"))
      (node (ref "DIGIT_3_GREEN") (pin "7") (pinfunction "G_7") (pintype "passive"))
      (node (ref "DIGIT_4_YELL0") (pin "7") (pinfunction "G_7") (pintype "passive"))
      (node (ref "DIGIT_5_YELL0") (pin "7") (pinfunction "G_7") (pintype "passive"))
      (node (ref "MAX6955") (pin "30") (pinfunction "O17_30") (pintype "bidirectional"))
      (node (ref "PD2Y") (pin "A") (pinfunction "A_A") (pintype "passive"))
    )
    (net (code "19") (name "Net-(DIGIT_1_REDA-COM)") (class "Default")
      (node (ref "DIGIT_1_RED") (pin "13") (pinfunction "COM_13") (pintype "passive"))
      (node (ref "DIGIT_1_RED") (pin "14") (pinfunction "COM_14") (pintype "passive"))
      (node (ref "MAX6955") (pin "8") (pinfunction "O1_8") (pintype "bidirectional"))
    )
    (net (code "20") (name "Net-(DIGIT_3_GREENA-COM)") (class "Default")
      (node (ref "DEP2B") (pin "A") (pinfunction "A_A") (pintype "passive"))
      (node (ref "DIGIT_3_GREEN") (pin "13") (pinfunction "COM_13") (pintype "passive"))
      (node (ref "DIGIT_3_GREEN") (pin "14") (pinfunction "COM_14") (pintype "passive"))
      (node (ref "DIGIT_4_YELL0") (pin "3") (pinfunction "C_3") (pintype "passive"))
      (node (ref "DIGIT_5_YELL0") (pin "3") (pinfunction "C_3") (pintype "passive"))
      (node (ref "HUM1R") (pin "A") (pinfunction "A_A") (pintype "passive"))
      (node (ref "MAX6955") (pin "10") (pinfunction "O3_10") (pintype "bidirectional"))
    )
    (net (code "21") (name "Net-(LED1-PadA)") (class "Default")
      (node (ref "LED1") (pin "A") (pinfunction "A_A") (pintype "passive"))
      (node (ref "R1") (pin "1") (pinfunction "1_1") (pintype "passive"))
    )
    (net (code "22") (name "Net-(LED2-PadA)") (class "Default")
      (node (ref "LED2") (pin "A") (pinfunction "A_A") (pintype "passive"))
      (node (ref "R2") (pin "1") (pinfunction "1_1") (pintype "passive"))
    )
    (net (code "23") (name "Net-(LED3-PadA)") (class "Default")
      (node (ref "LED3") (pin "A") (pinfunction "A_A") (pintype "passive"))
      (node (ref "R3") (pin "1") (pinfunction "1_1") (pintype "passive"))
    )
    (net (code "24") (name "Net-(LED4-PadA)") (class "Default")
      (node (ref "LED4") (pin "A") (pinfunction "A_A") (pintype "passive"))
      (node (ref "R4") (pin "1") (pinfunction "1_1") (pintype "passive"))
    )
    (net (code "25") (name "Net-(LS1-2)") (class "Default")
      (node (ref "LS1") (pin "-") (pinfunction "2_-") (pintype "passive"))
      (node (ref "MAX6955") (pin "36") (pinfunction "P4_36") (pintype "bidirectional"))
    )
    (net (code "26") (name "Net-(MAX6955-AD0)") (class "Default")
      (node (ref "AD0") (pin "2") (pinfunction "2_2") (pintype "passive"))
      (node (ref "MAX6955") (pin "3") (pinfunction "AD0_3") (pintype "bidirectional"))
    )
    (net (code "27") (name "Net-(MAX6955-AD1)") (class "Default")
      (node (ref "AD1") (pin "2") (pinfunction "2_2") (pintype "passive"))
      (node (ref "MAX6955") (pin "6") (pinfunction "AD1_6") (pintype "bidirectional"))
    )
    (net (code "28") (name "Net-(MAX6955-ISET)") (class "Default")
      (node (ref "MAX6955") (pin "17") (pinfunction "ISET_17") (pintype "bidirectional"))
      (node (ref "RSET") (pin "1") (pinfunction "1_1") (pintype "passive"))
    )
    (net (code "29") (name "Net-(MAX6955-OSC)") (class "Default")
      (node (ref "C1") (pin "2") (pinfunction "2_2") (pintype "passive"))
      (node (ref "MAX6955") (pin "20") (pinfunction "OSC_20") (pintype "bidirectional"))
    )
    (net (code "30") (name "Net-(MAX6955-P0)") (class "Default")
      (node (ref "MAX6955") (pin "1") (pinfunction "P0_1") (pintype "bidirectional"))
      (node (ref "R1") (pin "2") (pinfunction "2_2") (pintype "passive"))
      (node (ref "SW1") (pin "8") (pinfunction "8_8") (pintype "passive"))
    )
    (net (code "31") (name "Net-(MAX6955-P1)") (class "Default")
      (node (ref "MAX6955") (pin "2") (pinfunction "P1_2") (pintype "bidirectional"))
      (node (ref "R2") (pin "2") (pinfunction "2_2") (pintype "passive"))
      (node (ref "SW1") (pin "7") (pinfunction "7_7") (pintype "passive"))
    )
    (net (code "32") (name "Net-(MAX6955-P2)") (class "Default")
      (node (ref "MAX6955") (pin "34") (pinfunction "P2_34") (pintype "bidirectional"))
      (node (ref "R3") (pin "2") (pinfunction "2_2") (pintype "passive"))
      (node (ref "SW1") (pin "6") (pinfunction "6_6") (pintype "passive"))
    )
    (net (code "33") (name "Net-(MAX6955-P3)") (class "Default")
      (node (ref "MAX6955") (pin "35") (pinfunction "P3_35") (pintype "bidirectional"))
      (node (ref "R4") (pin "2") (pinfunction "2_2") (pintype "passive"))
      (node (ref "SW1") (pin "5") (pinfunction "5_5") (pintype "passive"))
    )
    (net (code "34") (name "Net-(MAX6955-SCL)") (class "Default")
      (node (ref "MAX6955") (pin "5") (pinfunction "SCL_5") (pintype "bidirectional"))
      (node (ref "U$2") (pin "SCL_ESC") (pinfunction "SCL_ESC_SCL_ESC") (pintype "bidirectional"))
    )
    (net (code "35") (name "Net-(MAX6955-SDA)") (class "Default")
      (node (ref "MAX6955") (pin "4") (pinfunction "SDA_4") (pintype "bidirectional"))
      (node (ref "U$2") (pin "SDA_ESC") (pinfunction "SDA_ESC_SDA_ESC") (pintype "bidirectional"))
    )
    (net (code "36") (name "VCC") (class "Default")
      (node (ref "AD0") (pin "3") (pinfunction "3_3") (pintype "passive"))
      (node (ref "AD1") (pin "3") (pinfunction "3_3") (pintype "passive"))
      (node (ref "C2") (pin "1") (pinfunction "1_1") (pintype "passive"))
      (node (ref "MAX6955") (pin "19") (pinfunction "V+_19") (pintype "bidirectional"))
      (node (ref "MAX6955") (pin "21") (pinfunction "V+_21") (pintype "bidirectional"))
      (node (ref "SW1") (pin "1") (pinfunction "1_1") (pintype "passive"))
      (node (ref "SW1") (pin "2") (pinfunction "2_2") (pintype "passive"))
      (node (ref "SW1") (pin "3") (pinfunction "3_3") (pintype "passive"))
      (node (ref "SW1") (pin "4") (pinfunction "4_4") (pintype "passive"))
      (node (ref "U$2") (pin "3.3VP1") (pinfunction "3.3V_1_3.3VP1") (pintype "bidirectional"))
      (node (ref "U$2") (pin "3.3VP2") (pinfunction "3.3V_2_3.3VP2") (pintype "bidirectional"))
      (node (ref "U$2") (pin "3.3VP3") (pinfunction "3.3V_3_3.3VP3") (pintype "bidirectional"))
      (node (ref "U$2") (pin "3.3V_4") (pinfunction "3.3V_4_3.3V_4") (pintype "bidirectional"))
      (node (ref "U$2") (pin "3.3V_5") (pinfunction "3.3V_5_3.3V_5") (pintype "bidirectional"))
      (node (ref "U$2") (pin "3.3V_6") (pinfunction "3.3V_6_3.3V_6") (pintype "bidirectional"))
    )
    (net (code "37") (name "unconnected-(MAX6955-BLINK-Pad32)") (class "Default")
      (node (ref "MAX6955") (pin "32") (pinfunction "BLINK_32") (pintype "bidirectional"))
    )
    (net (code "38") (name "unconnected-(MAX6955-OSC_OUT-Pad33)") (class "Default")
      (node (ref "MAX6955") (pin "33") (pinfunction "OSC_OUT_33") (pintype "bidirectional"))
    )
    (net (code "39") (name "unconnected-(U$2-PadCAN_H)") (class "Default")
      (node (ref "U$2") (pin "CAN_H") (pinfunction "CAN_H_CAN_H") (pintype "bidirectional"))
    )
    (net (code "40") (name "unconnected-(U$2-PadCAN_L)") (class "Default")
      (node (ref "U$2") (pin "CAN_L") (pinfunction "CAN_L_CAN_L") (pintype "bidirectional"))
    )
    (net (code "41") (name "unconnected-(U$2-PadEXTRA1)") (class "Default")
      (node (ref "U$2") (pin "EXTRA1") (pinfunction "EXTRA1_EXTRA1") (pintype "bidirectional"))
    )
    (net (code "42") (name "unconnected-(U$2-PadEXTRA2)") (class "Default")
      (node (ref "U$2") (pin "EXTRA2") (pinfunction "EXTRA2_EXTRA2") (pintype "bidirectional"))
    )
    (net (code "43") (name "unconnected-(U$2-PadEXTRA3)") (class "Default")
      (node (ref "U$2") (pin "EXTRA3") (pinfunction "EXTRA3_EXTRA3") (pintype "bidirectional"))
    )
    (net (code "44") (name "unconnected-(U$2-PadEXTRA4)") (class "Default")
      (node (ref "U$2") (pin "EXTRA4") (pinfunction "EXTRA4_EXTRA4") (pintype "bidirectional"))
    )
    (net (code "45") (name "unconnected-(U$2-PadEXTRA5)") (class "Default")
      (node (ref "U$2") (pin "EXTRA5") (pinfunction "EXTRA5_EXTRA5") (pintype "bidirectional"))
    )
    (net (code "46") (name "unconnected-(U$2-PadEXTRA6)") (class "Default")
      (node (ref "U$2") (pin "EXTRA6") (pinfunction "EXTRA6_EXTRA6") (pintype "bidirectional"))
    )
    (net (code "47") (name "unconnected-(U$2-PadEXTRA7)") (class "Default")
      (node (ref "U$2") (pin "EXTRA7") (pinfunction "EXTRA7_EXTRA7") (pintype "bidirectional"))
    )
    (net (code "48") (name "unconnected-(U$2-PadEXTRA8)") (class "Default")
      (node (ref "U$2") (pin "EXTRA8") (pinfunction "EXTRA8_EXTRA8") (pintype "bidirectional"))
    )
    (net (code "49") (name "unconnected-(U$2-PadEXTRA9)") (class "Default")
      (node (ref "U$2") (pin "EXTRA9") (pinfunction "EXTRA9_EXTRA9") (pintype "bidirectional"))
    )
    (net (code "50") (name "unconnected-(U$2-PadEXTRA10)") (class "Default")
      (node (ref "U$2") (pin "EXTRA10") (pinfunction "EXTRA10_EXTRA10") (pintype "bidirectional"))
    )
    (net (code "51") (name "unconnected-(U$2-PadEXTRA11)") (class "Default")
      (node (ref "U$2") (pin "EXTRA11") (pinfunction "EXTRA11_EXTRA11") (pintype "bidirectional"))
    )
    (net (code "52") (name "unconnected-(U$2-PadEXTRA12)") (class "Default")
      (node (ref "U$2") (pin "EXTRA12") (pinfunction "EXTRA12_EXTRA12") (pintype "bidirectional"))
    )
    (net (code "53") (name "unconnected-(U$2-PadEXTRA13)") (class "Default")
      (node (ref "U$2") (pin "EXTRA13") (pinfunction "EXTRA13_EXTRA13") (pintype "bidirectional"))
    )
    (net (code "54") (name "unconnected-(U$2-PadEXTRA14)") (class "Default")
      (node (ref "U$2") (pin "EXTRA14") (pinfunction "EXTRA14_EXTRA14") (pintype "bidirectional"))
    )
    (net (code "55") (name "unconnected-(U$2-PadEXTRA15)") (class "Default")
      (node (ref "U$2") (pin "EXTRA15") (pinfunction "EXTRA15_EXTRA15") (pintype "bidirectional"))
    )
    (net (code "56") (name "unconnected-(U$2-PadEXTRA16)") (class "Default")
      (node (ref "U$2") (pin "EXTRA16") (pinfunction "EXTRA16_EXTRA16") (pintype "bidirectional"))
    )
    (net (code "57") (name "unconnected-(U$2-PadEXTRA17)") (class "Default")
      (node (ref "U$2") (pin "EXTRA17") (pinfunction "EXTRA17_EXTRA17") (pintype "bidirectional"))
    )
    (net (code "58") (name "unconnected-(U$2-PadEXTRA18)") (class "Default")
      (node (ref "U$2") (pin "EXTRA18") (pinfunction "EXTRA18_EXTRA18") (pintype "bidirectional"))
    )
    (net (code "59") (name "unconnected-(U$2-PadEXTRA19)") (class "Default")
      (node (ref "U$2") (pin "EXTRA19") (pinfunction "EXTRA19_EXTRA19") (pintype "bidirectional"))
    )
    (net (code "60") (name "unconnected-(U$2-PadEXTRA20)") (class "Default")
      (node (ref "U$2") (pin "EXTRA20") (pinfunction "EXTRA20_EXTRA20") (pintype "bidirectional"))
    )
    (net (code "61") (name "unconnected-(U$2-PadEXTRA21)") (class "Default")
      (node (ref "U$2") (pin "EXTRA21") (pinfunction "EXTRA21_EXTRA21") (pintype "bidirectional"))
    )
    (net (code "62") (name "unconnected-(U$2-PadEXTRA22)") (class "Default")
      (node (ref "U$2") (pin "EXTRA22") (pinfunction "EXTRA22_EXTRA22") (pintype "bidirectional"))
    )
    (net (code "63") (name "unconnected-(U$2-PadEXTRA23)") (class "Default")
      (node (ref "U$2") (pin "EXTRA23") (pinfunction "EXTRA23_EXTRA23") (pintype "bidirectional"))
    )
    (net (code "64") (name "unconnected-(U$2-PadEXTRA24)") (class "Default")
      (node (ref "U$2") (pin "EXTRA24") (pinfunction "EXTRA24_EXTRA24") (pintype "bidirectional"))
    )
    (net (code "65") (name "unconnected-(U$2-PadEXTRA25)") (class "Default")
      (node (ref "U$2") (pin "EXTRA25") (pinfunction "EXTRA25_EXTRA25") (pintype "bidirectional"))
    )
    (net (code "66") (name "unconnected-(U$2-PadEXTRA26)") (class "Default")
      (node (ref "U$2") (pin "EXTRA26") (pinfunction "EXTRA26_EXTRA26") (pintype "bidirectional"))
    )
    (net (code "67") (name "unconnected-(U$2-PadEXTRA27)") (class "Default")
      (node (ref "U$2") (pin "EXTRA27") (pinfunction "EXTRA27_EXTRA27") (pintype "bidirectional"))
    )
    (net (code "68") (name "unconnected-(U$2-PadEXTRA28)") (class "Default")
      (node (ref "U$2") (pin "EXTRA28") (pinfunction "EXTRA28_EXTRA28") (pintype "bidirectional"))
    )
    (net (code "69") (name "unconnected-(U$2-PadEXTRA29)") (class "Default")
      (node (ref "U$2") (pin "EXTRA29") (pinfunction "EXTRA29_EXTRA29") (pintype "bidirectional"))
    )
    (net (code "70") (name "unconnected-(U$2-PadEXTRA30)") (class "Default")
      (node (ref "U$2") (pin "EXTRA30") (pinfunction "EXTRA30_EXTRA30") (pintype "bidirectional"))
    )
    (net (code "71") (name "unconnected-(U$2-PadEXTRA31)") (class "Default")
      (node (ref "U$2") (pin "EXTRA31") (pinfunction "EXTRA31_EXTRA31") (pintype "bidirectional"))
    )
    (net (code "72") (name "unconnected-(U$2-PadEXTRA32)") (class "Default")
      (node (ref "U$2") (pin "EXTRA32") (pinfunction "EXTRA32_EXTRA32") (pintype "bidirectional"))
    )
    (net (code "73") (name "unconnected-(U$2-PadEXTRA33)") (class "Default")
      (node (ref "U$2") (pin "EXTRA33") (pinfunction "EXTRA33_EXTRA33") (pintype "bidirectional"))
    )
    (net (code "74") (name "unconnected-(U$2-PadEXTRA34)") (class "Default")
      (node (ref "U$2") (pin "EXTRA34") (pinfunction "EXTRA34_EXTRA34") (pintype "bidirectional"))
    )
    (net (code "75") (name "unconnected-(U$2-PadEXTRA35)") (class "Default")
      (node (ref "U$2") (pin "EXTRA35") (pinfunction "EXTRA35_EXTRA35") (pintype "bidirectional"))
    )
    (net (code "76") (name "unconnected-(U$2-PadKILL_SWITCH)") (class "Default")
      (node (ref "U$2") (pin "KILL_SWITCH") (pinfunction "KILL_SWITCH_KILL_SWITCH") (pintype "bidirectional"))
    )
    (net (code "77") (name "unconnected-(U$2-PadSCL_DEPTH)") (class "Default")
      (node (ref "U$2") (pin "SCL_DEPTH") (pinfunction "SCL_DEPTH_SCL_DEPTH") (pintype "bidirectional"))
    )
    (net (code "78") (name "unconnected-(U$2-PadSCL_SENSOR)") (class "Default")
      (node (ref "U$2") (pin "SCL_SENSOR") (pinfunction "SCL_SENSOR_SCL_SENSOR") (pintype "bidirectional"))
    )
    (net (code "79") (name "unconnected-(U$2-PadSDA_DEPTH)") (class "Default")
      (node (ref "U$2") (pin "SDA_DEPTH") (pinfunction "SDA_DEPTH_SDA_DEPTH") (pintype "bidirectional"))
    )
    (net (code "80") (name "unconnected-(U$2-PadSDA_SENSOR)") (class "Default")
      (node (ref "U$2") (pin "SDA_SENSOR") (pinfunction "SDA_SENSOR_SDA_SENSOR") (pintype "bidirectional"))
    )
  )
)
